# TurrisClock.net
KiCad netlist of a schematic drawn in EAGLE
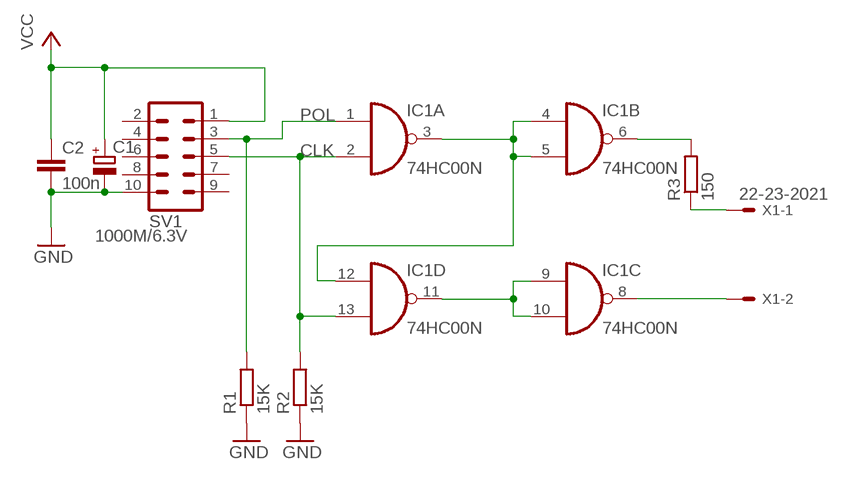
[diagram p0: schematic, sheet 1]

(export (version "E")
  (design (tool "Eeschema 10.0.6"))
  (components
    (comp (ref "C1")
      (value "1000M/6.3V")
      (footprint "eagle-import:E5-8,5")
      (libsource (lib "eagle-import") (part "CPOL-EUE5-8.5"))
    )
    (comp (ref "C2")
      (value "100n")
      (footprint "eagle-import:C050-024X044")
      (libsource (lib "eagle-import") (part "C-EU050-024X044"))
    )
    (comp (ref "IC1")
      (value "74HC00N")
      (footprint "eagle-import:DIL14")
      (libsource (lib "eagle-import") (part "7400NHC"))
    )
    (comp (ref "R1")
      (value "15K")
      (footprint "eagle-import:0204_7")
      (libsource (lib "eagle-import") (part "R-EU_0204/7"))
    )
    (comp (ref "R2")
      (value "15K")
      (footprint "eagle-import:0204_7")
      (libsource (lib "eagle-import") (part "R-EU_0204/7"))
    )
    (comp (ref "R3")
      (value "150")
      (footprint "eagle-import:0204_7")
      (libsource (lib "eagle-import") (part "R-EU_0204/7"))
    )
    (comp (ref "SV1")
      (value "ML10")
      (footprint "eagle-import:ML10")
      (libsource (lib "eagle-import") (part "ML10"))
    )
    (comp (ref "X1")
      (value "22-23-2021")
      (footprint "eagle-import:22-23-2021")
      (fields (field (name "MF") "MOLEX"))
      (libsource (lib "eagle-import") (part "22-23-2021"))
    )
  )
  (nets
    (net (code "1") (name "/CLK") (class "Default")
      (node (ref "IC1") (pin "13") (pinfunction "I1_13") (pintype "input"))
      (node (ref "IC1") (pin "2") (pinfunction "I1_2") (pintype "input"))
      (node (ref "R2") (pin "2") (pinfunction "2_2") (pintype "passive"))
      (node (ref "SV1") (pin "5") (pinfunction "5_5") (pintype "passive"))
    )
    (net (code "2") (name "/POL") (class "Default")
      (node (ref "IC1") (pin "1") (pinfunction "I0_1") (pintype "input"))
      (node (ref "R1") (pin "2") (pinfunction "2_2") (pintype "passive"))
      (node (ref "SV1") (pin "3") (pinfunction "3_3") (pintype "passive"))
    )
    (net (code "3") (name "GND") (class "Default")
      (node (ref "C1") (pin "-") (pinfunction "-_-") (pintype "passive"))
      (node (ref "C2") (pin "2") (pinfunction "2_2") (pintype "passive"))
      (node (ref "R1") (pin "1") (pinfunction "1_1") (pintype "passive"))
      (node (ref "R2") (pin "1") (pinfunction "1_1") (pintype "passive"))
      (node (ref "SV1") (pin "10") (pinfunction "10_10") (pintype "passive"))
    )
    (net (code "4") (name "Net-(IC1A-O)") (class "Default")
      (node (ref "IC1") (pin "12") (pinfunction "I0_12") (pintype "input"))
      (node (ref "IC1") (pin "3") (pinfunction "O_3") (pintype "output"))
      (node (ref "IC1") (pin "4") (pinfunction "I0_4") (pintype "input"))
      (node (ref "IC1") (pin "5") (pinfunction "I1_5") (pintype "input"))
    )
    (net (code "5") (name "Net-(IC1B-O)") (class "Default")
      (node (ref "IC1") (pin "6") (pinfunction "O_6") (pintype "output"))
      (node (ref "R3") (pin "2") (pinfunction "2_2") (pintype "passive"))
    )
    (net (code "6") (name "Net-(IC1C-I0)") (class "Default")
      (node (ref "IC1") (pin "10") (pinfunction "I1_10") (pintype "input"))
      (node (ref "IC1") (pin "11") (pinfunction "O_11") (pintype "output"))
      (node (ref "IC1") (pin "9") (pinfunction "I0_9") (pintype "input"))
    )
    (net (code "7") (name "Net-(IC1C-O)") (class "Default")
      (node (ref "IC1") (pin "8") (pinfunction "O_8") (pintype "output"))
      (node (ref "X1") (pin "2") (pinfunction "S_2") (pintype "passive"))
    )
    (net (code "8") (name "Net-(X1A-S)") (class "Default")
      (node (ref "R3") (pin "1") (pinfunction "1_1") (pintype "passive"))
      (node (ref "X1") (pin "1") (pinfunction "S_1") (pintype "passive"))
    )
    (net (code "9") (name "VCC") (class "Default")
      (node (ref "C1") (pin "+") (pinfunction "+_+") (pintype "passive"))
      (node (ref "C2") (pin "1") (pinfunction "1_1") (pintype "passive"))
      (node (ref "SV1") (pin "1") (pinfunction "1_1") (pintype "passive"))
    )
    (net (code "10") (name "unconnected-(SV1-Pad2)") (class "Default")
      (node (ref "SV1") (pin "2") (pinfunction "2_2") (pintype "passive"))
    )
    (net (code "11") (name "unconnected-(SV1-Pad4)") (class "Default")
      (node (ref "SV1") (pin "4") (pinfunction "4_4") (pintype "passive"))
    )
    (net (code "12") (name "unconnected-(SV1-Pad6)") (class "Default")
      (node (ref "SV1") (pin "6") (pinfunction "6_6") (pintype "passive"))
    )
    (net (code "13") (name "unconnected-(SV1-Pad7)") (class "Default")
      (node (ref "SV1") (pin "7") (pinfunction "7_7") (pintype "passive"))
    )
    (net (code "14") (name "unconnected-(SV1-Pad8)") (class "Default")
      (node (ref "SV1") (pin "8") (pinfunction "8_8") (pintype "passive"))
    )
    (net (code "15") (name "unconnected-(SV1-Pad9)") (class "Default")
      (node (ref "SV1") (pin "9") (pinfunction "9_9") (pintype "passive"))
    )
  )
)
